# PMI_Action_Octopus.net
KiCad netlist of a schematic drawn in Altium Designer
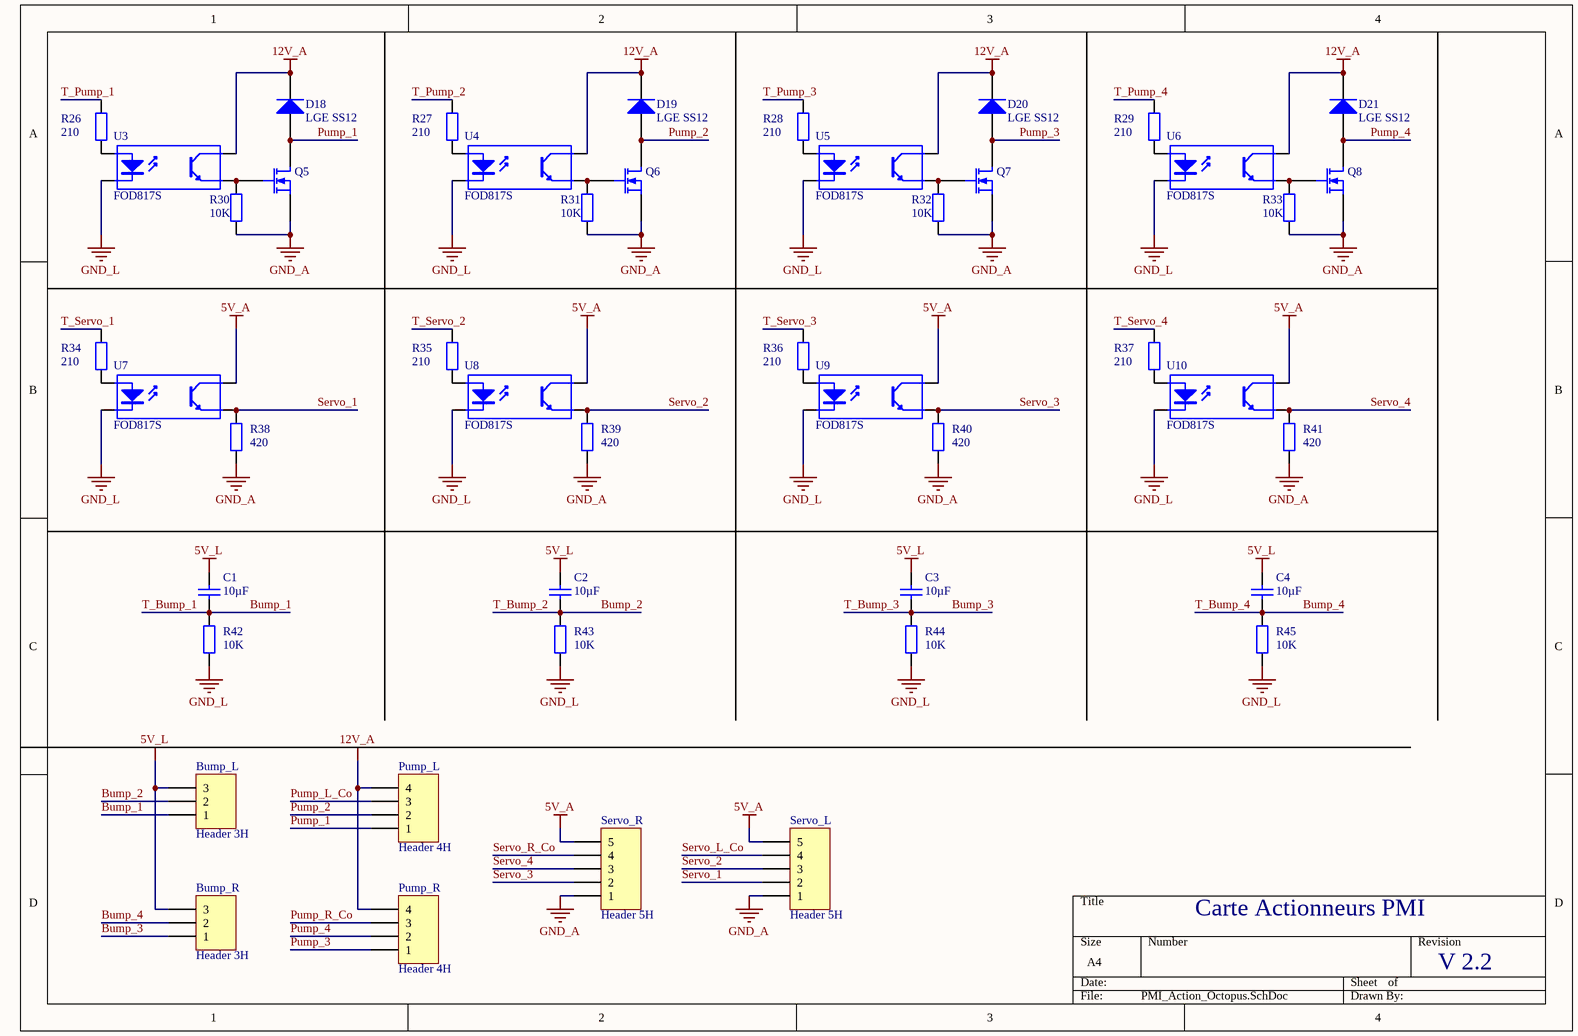
[diagram p0: PMI_Action_Octopus.SchDoc]

(export (version "E")
  (design (tool "Eeschema 10.0.6"))
  (components
    (comp (ref "Bump_L")
      (value "Header 3H")
      (footprint "S3B-XH-A")
      (description "Header, 3-Pin, Right Angle")
      (fields (field (name "PUBLISHER") "Altium Limited"))
      (libsource (lib "Miscellaneous Connectors") (part "Header 3H"))
    )
    (comp (ref "Bump_R")
      (value "Header 3H")
      (footprint "S3B-XH-A")
      (description "Header, 3-Pin, Right Angle")
      (fields (field (name "PUBLISHER") "Altium Limited"))
      (libsource (lib "Miscellaneous Connectors") (part "Header 3H"))
    )
    (comp (ref "C1")
      (value "10µF")
      (footprint "Capacitor 1206")
      (description "Capacitor")
      (fields (field (name "PUBLISHER") "Altium Limited"))
      (libsource (lib "Miscellaneous Devices") (part "Cap"))
    )
    (comp (ref "C2")
      (value "10µF")
      (footprint "Capacitor 1206")
      (description "Capacitor")
      (fields (field (name "PUBLISHER") "Altium Limited"))
      (libsource (lib "Miscellaneous Devices") (part "Cap"))
    )
    (comp (ref "C3")
      (value "10µF")
      (footprint "Capacitor 1206")
      (description "Capacitor")
      (fields (field (name "PUBLISHER") "Altium Limited"))
      (libsource (lib "Miscellaneous Devices") (part "Cap"))
    )
    (comp (ref "C4")
      (value "10µF")
      (footprint "Capacitor 1206")
      (description "Capacitor")
      (fields (field (name "PUBLISHER") "Altium Limited"))
      (libsource (lib "Miscellaneous Devices") (part "Cap"))
    )
    (comp (ref "D18")
      (value "LGE SS12")
      (footprint "SMB")
      (description "Default Diode")
      (fields (field (name "PUBLISHER") "Altium Limited"))
      (libsource (lib "Miscellaneous Devices") (part "Diode"))
    )
    (comp (ref "D19")
      (value "LGE SS12")
      (footprint "SMB")
      (description "Default Diode")
      (fields (field (name "PUBLISHER") "Altium Limited"))
      (libsource (lib "Miscellaneous Devices") (part "Diode"))
    )
    (comp (ref "D20")
      (value "LGE SS12")
      (footprint "SMB")
      (description "Default Diode")
      (fields (field (name "PUBLISHER") "Altium Limited"))
      (libsource (lib "Miscellaneous Devices") (part "Diode"))
    )
    (comp (ref "D21")
      (value "LGE SS12")
      (footprint "SMB")
      (description "Default Diode")
      (fields (field (name "PUBLISHER") "Altium Limited"))
      (libsource (lib "Miscellaneous Devices") (part "Diode"))
    )
    (comp (ref "Pump_L")
      (value "Header 4H")
      (footprint "S4B-XH-A")
      (description "Header, 4-Pin, Right Angle")
      (fields (field (name "PUBLISHER") "Altium Limited"))
      (libsource (lib "Miscellaneous Connectors") (part "Header 4H"))
    )
    (comp (ref "Pump_R")
      (value "Header 4H")
      (footprint "S4B-XH-A")
      (description "Header, 4-Pin, Right Angle")
      (fields (field (name "PUBLISHER") "Altium Limited"))
      (libsource (lib "Miscellaneous Connectors") (part "Header 4H"))
    )
    (comp (ref "Q5")
      (value "MOSFET-N")
      (footprint "SOT23_M")
      (description "N-Channel MOSFET")
      (fields (field (name "PUBLISHER") "Altium Limited"))
      (libsource (lib "Miscellaneous Devices") (part "MOSFET-N"))
    )
    (comp (ref "Q6")
      (value "MOSFET-N")
      (footprint "SOT23_M")
      (description "N-Channel MOSFET")
      (fields (field (name "PUBLISHER") "Altium Limited"))
      (libsource (lib "Miscellaneous Devices") (part "MOSFET-N"))
    )
    (comp (ref "Q7")
      (value "MOSFET-N")
      (footprint "SOT23_M")
      (description "N-Channel MOSFET")
      (fields (field (name "PUBLISHER") "Altium Limited"))
      (libsource (lib "Miscellaneous Devices") (part "MOSFET-N"))
    )
    (comp (ref "Q8")
      (value "MOSFET-N")
      (footprint "SOT23_M")
      (description "N-Channel MOSFET")
      (fields (field (name "PUBLISHER") "Altium Limited"))
      (libsource (lib "Miscellaneous Devices") (part "MOSFET-N"))
    )
    (comp (ref "R26")
      (value "210")
      (footprint "Resistor 1206")
      (description "Resistor")
      (fields (field (name "Comment") "Res2") (field (name "PUBLISHER") "Altium Limited"))
      (libsource (lib "Miscellaneous Devices") (part "Res2"))
    )
    (comp (ref "R27")
      (value "210")
      (footprint "Resistor 1206")
      (description "Resistor")
      (fields (field (name "Comment") "Res2") (field (name "PUBLISHER") "Altium Limited"))
      (libsource (lib "Miscellaneous Devices") (part "Res2"))
    )
    (comp (ref "R28")
      (value "210")
      (footprint "Resistor 1206")
      (description "Resistor")
      (fields (field (name "Comment") "Res2") (field (name "PUBLISHER") "Altium Limited"))
      (libsource (lib "Miscellaneous Devices") (part "Res2"))
    )
    (comp (ref "R29")
      (value "210")
      (footprint "Resistor 1206")
      (description "Resistor")
      (fields (field (name "Comment") "Res2") (field (name "PUBLISHER") "Altium Limited"))
      (libsource (lib "Miscellaneous Devices") (part "Res2"))
    )
    (comp (ref "R30")
      (value "10K")
      (footprint "Resistor 1206")
      (description "Resistor")
      (fields (field (name "Comment") "Res2") (field (name "PUBLISHER") "Altium Limited"))
      (libsource (lib "Miscellaneous Devices") (part "Res2"))
    )
    (comp (ref "R31")
      (value "10K")
      (footprint "Resistor 1206")
      (description "Resistor")
      (fields (field (name "Comment") "Res2") (field (name "PUBLISHER") "Altium Limited"))
      (libsource (lib "Miscellaneous Devices") (part "Res2"))
    )
    (comp (ref "R32")
      (value "10K")
      (footprint "Resistor 1206")
      (description "Resistor")
      (fields (field (name "Comment") "Res2") (field (name "PUBLISHER") "Altium Limited"))
      (libsource (lib "Miscellaneous Devices") (part "Res2"))
    )
    (comp (ref "R33")
      (value "10K")
      (footprint "Resistor 1206")
      (description "Resistor")
      (fields (field (name "Comment") "Res2") (field (name "PUBLISHER") "Altium Limited"))
      (libsource (lib "Miscellaneous Devices") (part "Res2"))
    )
    (comp (ref "R34")
      (value "210")
      (footprint "Resistor 1206")
      (description "Resistor")
      (fields (field (name "Comment") "Res2") (field (name "PUBLISHER") "Altium Limited"))
      (libsource (lib "Miscellaneous Devices") (part "Res2"))
    )
    (comp (ref "R35")
      (value "210")
      (footprint "Resistor 1206")
      (description "Resistor")
      (fields (field (name "Comment") "Res2") (field (name "PUBLISHER") "Altium Limited"))
      (libsource (lib "Miscellaneous Devices") (part "Res2"))
    )
    (comp (ref "R36")
      (value "210")
      (footprint "Resistor 1206")
      (description "Resistor")
      (fields (field (name "Comment") "Res2") (field (name "PUBLISHER") "Altium Limited"))
      (libsource (lib "Miscellaneous Devices") (part "Res2"))
    )
    (comp (ref "R37")
      (value "210")
      (footprint "Resistor 1206")
      (description "Resistor")
      (fields (field (name "Comment") "Res2") (field (name "PUBLISHER") "Altium Limited"))
      (libsource (lib "Miscellaneous Devices") (part "Res2"))
    )
    (comp (ref "R38")
      (value "420")
      (footprint "Resistor 1206")
      (description "Resistor")
      (fields (field (name "Comment") "Res2") (field (name "PUBLISHER") "Altium Limited"))
      (libsource (lib "Miscellaneous Devices") (part "Res2"))
    )
    (comp (ref "R39")
      (value "420")
      (footprint "Resistor 1206")
      (description "Resistor")
      (fields (field (name "Comment") "Res2") (field (name "PUBLISHER") "Altium Limited"))
      (libsource (lib "Miscellaneous Devices") (part "Res2"))
    )
    (comp (ref "R40")
      (value "420")
      (footprint "Resistor 1206")
      (description "Resistor")
      (fields (field (name "Comment") "Res2") (field (name "PUBLISHER") "Altium Limited"))
      (libsource (lib "Miscellaneous Devices") (part "Res2"))
    )
    (comp (ref "R41")
      (value "420")
      (footprint "Resistor 1206")
      (description "Resistor")
      (fields (field (name "Comment") "Res2") (field (name "PUBLISHER") "Altium Limited"))
      (libsource (lib "Miscellaneous Devices") (part "Res2"))
    )
    (comp (ref "R42")
      (value "10K")
      (footprint "Resistor 1206")
      (description "Resistor")
      (fields (field (name "Comment") "Res2") (field (name "PUBLISHER") "Altium Limited"))
      (libsource (lib "Miscellaneous Devices") (part "Res2"))
    )
    (comp (ref "R43")
      (value "10K")
      (footprint "Resistor 1206")
      (description "Resistor")
      (fields (field (name "Comment") "Res2") (field (name "PUBLISHER") "Altium Limited"))
      (libsource (lib "Miscellaneous Devices") (part "Res2"))
    )
    (comp (ref "R44")
      (value "10K")
      (footprint "Resistor 1206")
      (description "Resistor")
      (fields (field (name "Comment") "Res2") (field (name "PUBLISHER") "Altium Limited"))
      (libsource (lib "Miscellaneous Devices") (part "Res2"))
    )
    (comp (ref "R45")
      (value "10K")
      (footprint "Resistor 1206")
      (description "Resistor")
      (fields (field (name "Comment") "Res2") (field (name "PUBLISHER") "Altium Limited"))
      (libsource (lib "Miscellaneous Devices") (part "Res2"))
    )
    (comp (ref "Servo_L")
      (value "Header 5H")
      (footprint "S5B-XH-A")
      (description "Header, 5-Pin, Right Angle")
      (fields (field (name "PUBLISHER") "Altium Limited"))
      (libsource (lib "Miscellaneous Connectors") (part "Header 5H"))
    )
    (comp (ref "Servo_R")
      (value "Header 5H")
      (footprint "S5B-XH-A")
      (description "Header, 5-Pin, Right Angle")
      (fields (field (name "PUBLISHER") "Altium Limited"))
      (libsource (lib "Miscellaneous Connectors") (part "Header 5H"))
    )
    (comp (ref "U3")
      (value "FOD817S")
      (footprint "SOP254P1016X385-4N")
      (description "4-Pin Phototransistor Optocoupler")
      (fields (field (name "PUBLISHER") "Altium Limited"))
      (libsource (lib "Miscellaneous Devices") (part "Optoisolator1"))
    )
    (comp (ref "U4")
      (value "FOD817S")
      (footprint "SOP254P1016X385-4N")
      (description "4-Pin Phototransistor Optocoupler")
      (fields (field (name "PUBLISHER") "Altium Limited"))
      (libsource (lib "Miscellaneous Devices") (part "Optoisolator1"))
    )
    (comp (ref "U5")
      (value "FOD817S")
      (footprint "SOP254P1016X385-4N")
      (description "4-Pin Phototransistor Optocoupler")
      (fields (field (name "PUBLISHER") "Altium Limited"))
      (libsource (lib "Miscellaneous Devices") (part "Optoisolator1"))
    )
    (comp (ref "U6")
      (value "FOD817S")
      (footprint "SOP254P1016X385-4N")
      (description "4-Pin Phototransistor Optocoupler")
      (fields (field (name "PUBLISHER") "Altium Limited"))
      (libsource (lib "Miscellaneous Devices") (part "Optoisolator1"))
    )
    (comp (ref "U7")
      (value "FOD817S")
      (footprint "SOP254P1016X385-4N")
      (description "4-Pin Phototransistor Optocoupler")
      (fields (field (name "PUBLISHER") "Altium Limited"))
      (libsource (lib "Miscellaneous Devices") (part "Optoisolator1"))
    )
    (comp (ref "U8")
      (value "FOD817S")
      (footprint "SOP254P1016X385-4N")
      (description "4-Pin Phototransistor Optocoupler")
      (fields (field (name "PUBLISHER") "Altium Limited"))
      (libsource (lib "Miscellaneous Devices") (part "Optoisolator1"))
    )
    (comp (ref "U9")
      (value "FOD817S")
      (footprint "SOP254P1016X385-4N")
      (description "4-Pin Phototransistor Optocoupler")
      (fields (field (name "PUBLISHER") "Altium Limited"))
      (libsource (lib "Miscellaneous Devices") (part "Optoisolator1"))
    )
    (comp (ref "U10")
      (value "FOD817S")
      (footprint "SOP254P1016X385-4N")
      (description "4-Pin Phototransistor Optocoupler")
      (fields (field (name "PUBLISHER") "Altium Limited"))
      (libsource (lib "Miscellaneous Devices") (part "Optoisolator1"))
    )
  )
  (nets
    (net (code "1") (name "/Bump_1") (class "Default")
      (node (ref "Bump_L") (pin "1") (pinfunction "1_1") (pintype "passive"))
      (node (ref "C1") (pin "1") (pinfunction "1_1") (pintype "passive"))
      (node (ref "R42") (pin "2") (pinfunction "2_2") (pintype "passive"))
    )
    (net (code "2") (name "/Bump_2") (class "Default")
      (node (ref "Bump_L") (pin "2") (pinfunction "2_2") (pintype "passive"))
      (node (ref "C2") (pin "1") (pinfunction "1_1") (pintype "passive"))
      (node (ref "R43") (pin "2") (pinfunction "2_2") (pintype "passive"))
    )
    (net (code "3") (name "/Bump_3") (class "Default")
      (node (ref "Bump_R") (pin "1") (pinfunction "1_1") (pintype "passive"))
      (node (ref "C3") (pin "1") (pinfunction "1_1") (pintype "passive"))
      (node (ref "R44") (pin "2") (pinfunction "2_2") (pintype "passive"))
    )
    (net (code "4") (name "/Bump_4") (class "Default")
      (node (ref "Bump_R") (pin "2") (pinfunction "2_2") (pintype "passive"))
      (node (ref "C4") (pin "1") (pinfunction "1_1") (pintype "passive"))
      (node (ref "R45") (pin "2") (pinfunction "2_2") (pintype "passive"))
    )
    (net (code "5") (name "/Pump_1") (class "Default")
      (node (ref "D18") (pin "1") (pinfunction "A_1") (pintype "passive"))
      (node (ref "Pump_L") (pin "1") (pinfunction "1_1") (pintype "passive"))
      (node (ref "Q5") (pin "1") (pinfunction "D_1") (pintype "passive"))
    )
    (net (code "6") (name "/Pump_2") (class "Default")
      (node (ref "D19") (pin "1") (pinfunction "A_1") (pintype "passive"))
      (node (ref "Pump_L") (pin "2") (pinfunction "2_2") (pintype "passive"))
      (node (ref "Q6") (pin "1") (pinfunction "D_1") (pintype "passive"))
    )
    (net (code "7") (name "/Pump_3") (class "Default")
      (node (ref "D20") (pin "1") (pinfunction "A_1") (pintype "passive"))
      (node (ref "Pump_R") (pin "1") (pinfunction "1_1") (pintype "passive"))
      (node (ref "Q7") (pin "1") (pinfunction "D_1") (pintype "passive"))
    )
    (net (code "8") (name "/Pump_4") (class "Default")
      (node (ref "D21") (pin "1") (pinfunction "A_1") (pintype "passive"))
      (node (ref "Pump_R") (pin "2") (pinfunction "2_2") (pintype "passive"))
      (node (ref "Q8") (pin "1") (pinfunction "D_1") (pintype "passive"))
    )
    (net (code "9") (name "/Pump_L_Co") (class "Default")
      (node (ref "Pump_L") (pin "3") (pinfunction "3_3") (pintype "passive"))
    )
    (net (code "10") (name "/Pump_R_Co") (class "Default")
      (node (ref "Pump_R") (pin "3") (pinfunction "3_3") (pintype "passive"))
    )
    (net (code "11") (name "/Servo_1") (class "Default")
      (node (ref "R38") (pin "2") (pinfunction "2_2") (pintype "passive"))
      (node (ref "Servo_L") (pin "2") (pinfunction "2_2") (pintype "passive"))
      (node (ref "U7") (pin "3") (pinfunction "E_3") (pintype "passive"))
    )
    (net (code "12") (name "/Servo_2") (class "Default")
      (node (ref "R39") (pin "2") (pinfunction "2_2") (pintype "passive"))
      (node (ref "Servo_L") (pin "3") (pinfunction "3_3") (pintype "passive"))
      (node (ref "U8") (pin "3") (pinfunction "E_3") (pintype "passive"))
    )
    (net (code "13") (name "/Servo_3") (class "Default")
      (node (ref "R40") (pin "2") (pinfunction "2_2") (pintype "passive"))
      (node (ref "Servo_R") (pin "2") (pinfunction "2_2") (pintype "passive"))
      (node (ref "U9") (pin "3") (pinfunction "E_3") (pintype "passive"))
    )
    (net (code "14") (name "/Servo_4") (class "Default")
      (node (ref "R41") (pin "2") (pinfunction "2_2") (pintype "passive"))
      (node (ref "Servo_R") (pin "3") (pinfunction "3_3") (pintype "passive"))
      (node (ref "U10") (pin "3") (pinfunction "E_3") (pintype "passive"))
    )
    (net (code "15") (name "/Servo_L_Co") (class "Default")
      (node (ref "Servo_L") (pin "4") (pinfunction "4_4") (pintype "passive"))
    )
    (net (code "16") (name "/Servo_R_Co") (class "Default")
      (node (ref "Servo_R") (pin "4") (pinfunction "4_4") (pintype "passive"))
    )
    (net (code "17") (name "/T_Pump_1") (class "Default")
      (node (ref "R26") (pin "2") (pinfunction "2_2") (pintype "passive"))
    )
    (net (code "18") (name "/T_Pump_2") (class "Default")
      (node (ref "R27") (pin "2") (pinfunction "2_2") (pintype "passive"))
    )
    (net (code "19") (name "/T_Pump_3") (class "Default")
      (node (ref "R28") (pin "2") (pinfunction "2_2") (pintype "passive"))
    )
    (net (code "20") (name "/T_Pump_4") (class "Default")
      (node (ref "R29") (pin "2") (pinfunction "2_2") (pintype "passive"))
    )
    (net (code "21") (name "/T_Servo_1") (class "Default")
      (node (ref "R34") (pin "2") (pinfunction "2_2") (pintype "passive"))
    )
    (net (code "22") (name "/T_Servo_2") (class "Default")
      (node (ref "R35") (pin "2") (pinfunction "2_2") (pintype "passive"))
    )
    (net (code "23") (name "/T_Servo_3") (class "Default")
      (node (ref "R36") (pin "2") (pinfunction "2_2") (pintype "passive"))
    )
    (net (code "24") (name "/T_Servo_4") (class "Default")
      (node (ref "R37") (pin "2") (pinfunction "2_2") (pintype "passive"))
    )
    (net (code "25") (name "5V_A") (class "Default")
      (node (ref "Servo_L") (pin "5") (pinfunction "5_5") (pintype "passive"))
      (node (ref "Servo_R") (pin "5") (pinfunction "5_5") (pintype "passive"))
      (node (ref "U10") (pin "4") (pinfunction "C_4") (pintype "passive"))
      (node (ref "U7") (pin "4") (pinfunction "C_4") (pintype "passive"))
      (node (ref "U8") (pin "4") (pinfunction "C_4") (pintype "passive"))
      (node (ref "U9") (pin "4") (pinfunction "C_4") (pintype "passive"))
    )
    (net (code "26") (name "5V_L") (class "Default")
      (node (ref "Bump_L") (pin "3") (pinfunction "3_3") (pintype "passive"))
      (node (ref "Bump_R") (pin "3") (pinfunction "3_3") (pintype "passive"))
      (node (ref "C1") (pin "2") (pinfunction "2_2") (pintype "passive"))
      (node (ref "C2") (pin "2") (pinfunction "2_2") (pintype "passive"))
      (node (ref "C3") (pin "2") (pinfunction "2_2") (pintype "passive"))
      (node (ref "C4") (pin "2") (pinfunction "2_2") (pintype "passive"))
    )
    (net (code "27") (name "12V_A") (class "Default")
      (node (ref "D18") (pin "2") (pinfunction "K_2") (pintype "passive"))
      (node (ref "D19") (pin "2") (pinfunction "K_2") (pintype "passive"))
      (node (ref "D20") (pin "2") (pinfunction "K_2") (pintype "passive"))
      (node (ref "D21") (pin "2") (pinfunction "K_2") (pintype "passive"))
      (node (ref "Pump_L") (pin "4") (pinfunction "4_4") (pintype "passive"))
      (node (ref "Pump_R") (pin "4") (pinfunction "4_4") (pintype "passive"))
      (node (ref "U3") (pin "4") (pinfunction "C_4") (pintype "passive"))
      (node (ref "U4") (pin "4") (pinfunction "C_4") (pintype "passive"))
      (node (ref "U5") (pin "4") (pinfunction "C_4") (pintype "passive"))
      (node (ref "U6") (pin "4") (pinfunction "C_4") (pintype "passive"))
    )
    (net (code "28") (name "GND_A") (class "Default")
      (node (ref "Q5") (pin "3") (pinfunction "S_3") (pintype "passive"))
      (node (ref "Q6") (pin "3") (pinfunction "S_3") (pintype "passive"))
      (node (ref "Q7") (pin "3") (pinfunction "S_3") (pintype "passive"))
      (node (ref "Q8") (pin "3") (pinfunction "S_3") (pintype "passive"))
      (node (ref "R30") (pin "1") (pinfunction "1_1") (pintype "passive"))
      (node (ref "R31") (pin "1") (pinfunction "1_1") (pintype "passive"))
      (node (ref "R32") (pin "1") (pinfunction "1_1") (pintype "passive"))
      (node (ref "R33") (pin "1") (pinfunction "1_1") (pintype "passive"))
      (node (ref "R38") (pin "1") (pinfunction "1_1") (pintype "passive"))
      (node (ref "R39") (pin "1") (pinfunction "1_1") (pintype "passive"))
      (node (ref "R40") (pin "1") (pinfunction "1_1") (pintype "passive"))
      (node (ref "R41") (pin "1") (pinfunction "1_1") (pintype "passive"))
      (node (ref "Servo_L") (pin "1") (pinfunction "1_1") (pintype "passive"))
      (node (ref "Servo_R") (pin "1") (pinfunction "1_1") (pintype "passive"))
    )
    (net (code "29") (name "GND_L") (class "Default")
      (node (ref "R42") (pin "1") (pinfunction "1_1") (pintype "passive"))
      (node (ref "R43") (pin "1") (pinfunction "1_1") (pintype "passive"))
      (node (ref "R44") (pin "1") (pinfunction "1_1") (pintype "passive"))
      (node (ref "R45") (pin "1") (pinfunction "1_1") (pintype "passive"))
      (node (ref "U10") (pin "2") (pinfunction "K_2") (pintype "passive"))
      (node (ref "U3") (pin "2") (pinfunction "K_2") (pintype "passive"))
      (node (ref "U4") (pin "2") (pinfunction "K_2") (pintype "passive"))
      (node (ref "U5") (pin "2") (pinfunction "K_2") (pintype "passive"))
      (node (ref "U6") (pin "2") (pinfunction "K_2") (pintype "passive"))
      (node (ref "U7") (pin "2") (pinfunction "K_2") (pintype "passive"))
      (node (ref "U8") (pin "2") (pinfunction "K_2") (pintype "passive"))
      (node (ref "U9") (pin "2") (pinfunction "K_2") (pintype "passive"))
    )
    (net (code "30") (name "Net-(Q5-G)") (class "Default")
      (node (ref "Q5") (pin "2") (pinfunction "G_2") (pintype "passive"))
      (node (ref "R30") (pin "2") (pinfunction "2_2") (pintype "passive"))
      (node (ref "U3") (pin "3") (pinfunction "E_3") (pintype "passive"))
    )
    (net (code "31") (name "Net-(Q6-G)") (class "Default")
      (node (ref "Q6") (pin "2") (pinfunction "G_2") (pintype "passive"))
      (node (ref "R31") (pin "2") (pinfunction "2_2") (pintype "passive"))
      (node (ref "U4") (pin "3") (pinfunction "E_3") (pintype "passive"))
    )
    (net (code "32") (name "Net-(Q7-G)") (class "Default")
      (node (ref "Q7") (pin "2") (pinfunction "G_2") (pintype "passive"))
      (node (ref "R32") (pin "2") (pinfunction "2_2") (pintype "passive"))
      (node (ref "U5") (pin "3") (pinfunction "E_3") (pintype "passive"))
    )
    (net (code "33") (name "Net-(Q8-G)") (class "Default")
      (node (ref "Q8") (pin "2") (pinfunction "G_2") (pintype "passive"))
      (node (ref "R33") (pin "2") (pinfunction "2_2") (pintype "passive"))
      (node (ref "U6") (pin "3") (pinfunction "E_3") (pintype "passive"))
    )
    (net (code "34") (name "Net-(U3-A)") (class "Default")
      (node (ref "R26") (pin "1") (pinfunction "1_1") (pintype "passive"))
      (node (ref "U3") (pin "1") (pinfunction "A_1") (pintype "passive"))
    )
    (net (code "35") (name "Net-(U4-A)") (class "Default")
      (node (ref "R27") (pin "1") (pinfunction "1_1") (pintype "passive"))
      (node (ref "U4") (pin "1") (pinfunction "A_1") (pintype "passive"))
    )
    (net (code "36") (name "Net-(U5-A)") (class "Default")
      (node (ref "R28") (pin "1") (pinfunction "1_1") (pintype "passive"))
      (node (ref "U5") (pin "1") (pinfunction "A_1") (pintype "passive"))
    )
    (net (code "37") (name "Net-(U6-A)") (class "Default")
      (node (ref "R29") (pin "1") (pinfunction "1_1") (pintype "passive"))
      (node (ref "U6") (pin "1") (pinfunction "A_1") (pintype "passive"))
    )
    (net (code "38") (name "Net-(U7-A)") (class "Default")
      (node (ref "R34") (pin "1") (pinfunction "1_1") (pintype "passive"))
      (node (ref "U7") (pin "1") (pinfunction "A_1") (pintype "passive"))
    )
    (net (code "39") (name "Net-(U8-A)") (class "Default")
      (node (ref "R35") (pin "1") (pinfunction "1_1") (pintype "passive"))
      (node (ref "U8") (pin "1") (pinfunction "A_1") (pintype "passive"))
    )
    (net (code "40") (name "Net-(U9-A)") (class "Default")
      (node (ref "R36") (pin "1") (pinfunction "1_1") (pintype "passive"))
      (node (ref "U9") (pin "1") (pinfunction "A_1") (pintype "passive"))
    )
    (net (code "41") (name "Net-(U10-A)") (class "Default")
      (node (ref "R37") (pin "1") (pinfunction "1_1") (pintype "passive"))
      (node (ref "U10") (pin "1") (pinfunction "A_1") (pintype "passive"))
    )
  )
)
